# blues-hardware.net
KiCad netlist of a schematic drawn in EAGLE
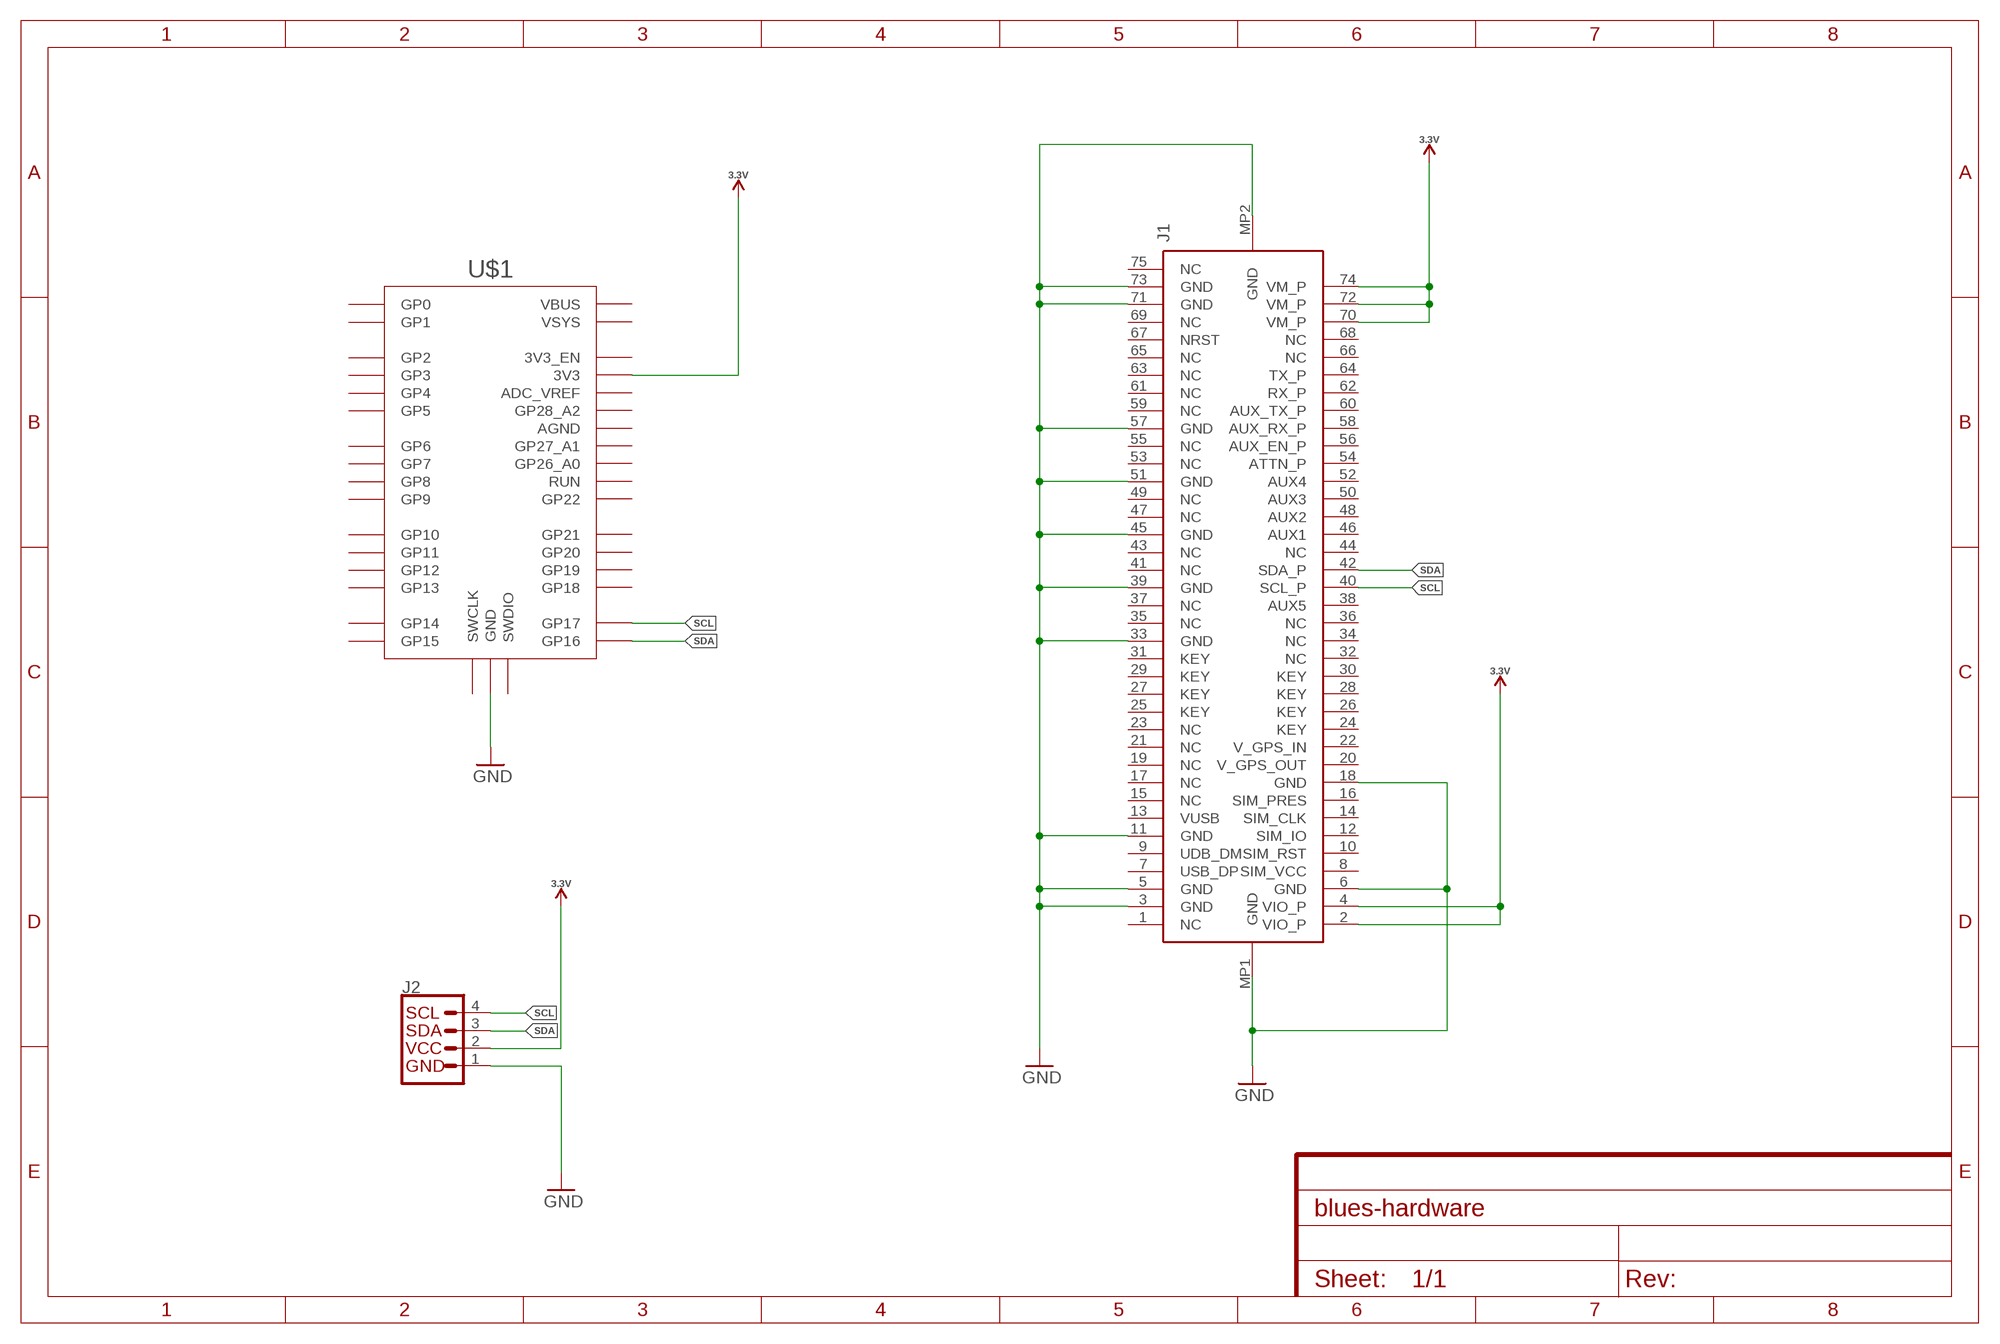
[diagram p0: schematic, sheet 1]

(export (version "E")
  (design (tool "Eeschema 10.0.6"))
  (components
    (comp (ref "J1")
      (value "MDT420E01001NOTECARD")
      (footprint "eagle-import:NOTECARD")
      (libsource (lib "eagle-import") (part "MDT420E01001NOTECARD"))
    )
    (comp (ref "J2")
      (value "QWIIC_CONNECTORJS-1MM")
      (footprint "eagle-import:1X04_1MM_RA")
      (libsource (lib "eagle-import") (part "QWIIC_CONNECTORJS-1MM"))
    )
    (comp (ref "U$1")
      (value "RPI_PICO-TH")
      (footprint "eagle-import:RPI_PICO_TH")
      (libsource (lib "eagle-import") (part "RPI_PICO-TH"))
    )
  )
  (nets
    (net (code "1") (name "3.3V") (class "Default")
      (node (ref "J1") (pin "2") (pinfunction "VIO_P_2") (pintype "bidirectional"))
      (node (ref "J1") (pin "4") (pinfunction "VIO_P_4") (pintype "bidirectional"))
      (node (ref "J1") (pin "70") (pinfunction "VM_P_70") (pintype "bidirectional"))
      (node (ref "J1") (pin "72") (pinfunction "VM_P_72") (pintype "bidirectional"))
      (node (ref "J1") (pin "74") (pinfunction "VM_P_74") (pintype "bidirectional"))
      (node (ref "J2") (pin "2") (pinfunction "2_2") (pintype "power_in"))
      (node (ref "U$1") (pin "3V3") (pinfunction "3V3_3V3") (pintype "bidirectional"))
    )
    (net (code "2") (name "GND") (class "Default")
      (node (ref "J1") (pin "11") (pinfunction "GND_11") (pintype "bidirectional"))
      (node (ref "J1") (pin "18") (pinfunction "GND_18") (pintype "bidirectional"))
      (node (ref "J1") (pin "3") (pinfunction "GND_3") (pintype "bidirectional"))
      (node (ref "J1") (pin "33") (pinfunction "GND_33") (pintype "bidirectional"))
      (node (ref "J1") (pin "39") (pinfunction "GND_39") (pintype "bidirectional"))
      (node (ref "J1") (pin "45") (pinfunction "GND_45") (pintype "bidirectional"))
      (node (ref "J1") (pin "5") (pinfunction "GND_5") (pintype "bidirectional"))
      (node (ref "J1") (pin "51") (pinfunction "GND_51") (pintype "bidirectional"))
      (node (ref "J1") (pin "57") (pinfunction "GND_57") (pintype "bidirectional"))
      (node (ref "J1") (pin "6") (pinfunction "GND_6") (pintype "bidirectional"))
      (node (ref "J1") (pin "71") (pinfunction "GND_71") (pintype "bidirectional"))
      (node (ref "J1") (pin "73") (pinfunction "GND_73") (pintype "bidirectional"))
      (node (ref "J1") (pin "MP1") (pinfunction "GND_MP1") (pintype "power_in"))
      (node (ref "J1") (pin "MP2") (pinfunction "GND_MP2") (pintype "bidirectional"))
      (node (ref "J2") (pin "1") (pinfunction "1_1") (pintype "power_in"))
      (node (ref "U$1") (pin "GND@1") (pinfunction "GND_GND@1") (pintype "bidirectional"))
      (node (ref "U$1") (pin "GND@2") (pinfunction "GND_GND@2") (pintype "bidirectional"))
      (node (ref "U$1") (pin "GND@3") (pinfunction "GND_GND@3") (pintype "bidirectional"))
      (node (ref "U$1") (pin "GND@4") (pinfunction "GND_GND@4") (pintype "bidirectional"))
      (node (ref "U$1") (pin "GND@5") (pinfunction "GND_GND@5") (pintype "bidirectional"))
      (node (ref "U$1") (pin "GND@6") (pinfunction "GND_GND@6") (pintype "bidirectional"))
      (node (ref "U$1") (pin "GND@7") (pinfunction "GND_GND@7") (pintype "bidirectional"))
      (node (ref "U$1") (pin "GND@8") (pinfunction "GND_GND@8") (pintype "bidirectional"))
    )
    (net (code "3") (name "SCL") (class "Default")
      (node (ref "J1") (pin "40") (pinfunction "SCL_P_40") (pintype "bidirectional"))
      (node (ref "J2") (pin "4") (pinfunction "4_4") (pintype "passive"))
      (node (ref "U$1") (pin "GP17") (pinfunction "GP17_GP17") (pintype "bidirectional"))
    )
    (net (code "4") (name "SDA") (class "Default")
      (node (ref "J1") (pin "42") (pinfunction "SDA_P_42") (pintype "bidirectional"))
      (node (ref "J2") (pin "3") (pinfunction "3_3") (pintype "passive"))
      (node (ref "U$1") (pin "GP16") (pinfunction "GP16_GP16") (pintype "bidirectional"))
    )
    (net (code "5") (name "unconnected-(J1-ATTN_P-Pad54)") (class "Default")
      (node (ref "J1") (pin "54") (pinfunction "ATTN_P_54") (pintype "bidirectional"))
    )
    (net (code "6") (name "unconnected-(J1-AUX1-Pad46)") (class "Default")
      (node (ref "J1") (pin "46") (pinfunction "AUX1_46") (pintype "bidirectional"))
    )
    (net (code "7") (name "unconnected-(J1-AUX2-Pad48)") (class "Default")
      (node (ref "J1") (pin "48") (pinfunction "AUX2_48") (pintype "bidirectional"))
    )
    (net (code "8") (name "unconnected-(J1-AUX3-Pad50)") (class "Default")
      (node (ref "J1") (pin "50") (pinfunction "AUX3_50") (pintype "bidirectional"))
    )
    (net (code "9") (name "unconnected-(J1-AUX4-Pad52)") (class "Default")
      (node (ref "J1") (pin "52") (pinfunction "AUX4_52") (pintype "bidirectional"))
    )
    (net (code "10") (name "unconnected-(J1-AUX5-Pad38)") (class "Default")
      (node (ref "J1") (pin "38") (pinfunction "AUX5_38") (pintype "bidirectional"))
    )
    (net (code "11") (name "unconnected-(J1-AUX_EN_P-Pad56)") (class "Default")
      (node (ref "J1") (pin "56") (pinfunction "AUX_EN_P_56") (pintype "bidirectional"))
    )
    (net (code "12") (name "unconnected-(J1-AUX_RX_P-Pad58)") (class "Default")
      (node (ref "J1") (pin "58") (pinfunction "AUX_RX_P_58") (pintype "bidirectional"))
    )
    (net (code "13") (name "unconnected-(J1-AUX_TX_P-Pad60)") (class "Default")
      (node (ref "J1") (pin "60") (pinfunction "AUX_TX_P_60") (pintype "bidirectional"))
    )
    (net (code "14") (name "unconnected-(J1-KEY-Pad24)") (class "Default")
      (node (ref "J1") (pin "24") (pinfunction "KEY_24") (pintype "bidirectional"))
    )
    (net (code "15") (name "unconnected-(J1-KEY-Pad25)") (class "Default")
      (node (ref "J1") (pin "25") (pinfunction "KEY_25") (pintype "bidirectional"))
    )
    (net (code "16") (name "unconnected-(J1-KEY-Pad26)") (class "Default")
      (node (ref "J1") (pin "26") (pinfunction "KEY_26") (pintype "bidirectional"))
    )
    (net (code "17") (name "unconnected-(J1-KEY-Pad27)") (class "Default")
      (node (ref "J1") (pin "27") (pinfunction "KEY_27") (pintype "bidirectional"))
    )
    (net (code "18") (name "unconnected-(J1-KEY-Pad28)") (class "Default")
      (node (ref "J1") (pin "28") (pinfunction "KEY_28") (pintype "bidirectional"))
    )
    (net (code "19") (name "unconnected-(J1-KEY-Pad29)") (class "Default")
      (node (ref "J1") (pin "29") (pinfunction "KEY_29") (pintype "bidirectional"))
    )
    (net (code "20") (name "unconnected-(J1-KEY-Pad30)") (class "Default")
      (node (ref "J1") (pin "30") (pinfunction "KEY_30") (pintype "bidirectional"))
    )
    (net (code "21") (name "unconnected-(J1-KEY-Pad31)") (class "Default")
      (node (ref "J1") (pin "31") (pinfunction "KEY_31") (pintype "bidirectional"))
    )
    (net (code "22") (name "unconnected-(J1-NC-Pad1)") (class "Default")
      (node (ref "J1") (pin "1") (pinfunction "NC_1") (pintype "bidirectional"))
    )
    (net (code "23") (name "unconnected-(J1-NC-Pad15)") (class "Default")
      (node (ref "J1") (pin "15") (pinfunction "NC_15") (pintype "bidirectional"))
    )
    (net (code "24") (name "unconnected-(J1-NC-Pad17)") (class "Default")
      (node (ref "J1") (pin "17") (pinfunction "NC_17") (pintype "bidirectional"))
    )
    (net (code "25") (name "unconnected-(J1-NC-Pad19)") (class "Default")
      (node (ref "J1") (pin "19") (pinfunction "NC_19") (pintype "bidirectional"))
    )
    (net (code "26") (name "unconnected-(J1-NC-Pad21)") (class "Default")
      (node (ref "J1") (pin "21") (pinfunction "NC_21") (pintype "bidirectional"))
    )
    (net (code "27") (name "unconnected-(J1-NC-Pad23)") (class "Default")
      (node (ref "J1") (pin "23") (pinfunction "NC_23") (pintype "bidirectional"))
    )
    (net (code "28") (name "unconnected-(J1-NC-Pad32)") (class "Default")
      (node (ref "J1") (pin "32") (pinfunction "NC_32") (pintype "bidirectional"))
    )
    (net (code "29") (name "unconnected-(J1-NC-Pad34)") (class "Default")
      (node (ref "J1") (pin "34") (pinfunction "NC_34") (pintype "bidirectional"))
    )
    (net (code "30") (name "unconnected-(J1-NC-Pad35)") (class "Default")
      (node (ref "J1") (pin "35") (pinfunction "NC_35") (pintype "bidirectional"))
    )
    (net (code "31") (name "unconnected-(J1-NC-Pad36)") (class "Default")
      (node (ref "J1") (pin "36") (pinfunction "NC_36") (pintype "bidirectional"))
    )
    (net (code "32") (name "unconnected-(J1-NC-Pad37)") (class "Default")
      (node (ref "J1") (pin "37") (pinfunction "NC_37") (pintype "bidirectional"))
    )
    (net (code "33") (name "unconnected-(J1-NC-Pad41)") (class "Default")
      (node (ref "J1") (pin "41") (pinfunction "NC_41") (pintype "bidirectional"))
    )
    (net (code "34") (name "unconnected-(J1-NC-Pad43)") (class "Default")
      (node (ref "J1") (pin "43") (pinfunction "NC_43") (pintype "bidirectional"))
    )
    (net (code "35") (name "unconnected-(J1-NC-Pad44)") (class "Default")
      (node (ref "J1") (pin "44") (pinfunction "NC_44") (pintype "bidirectional"))
    )
    (net (code "36") (name "unconnected-(J1-NC-Pad47)") (class "Default")
      (node (ref "J1") (pin "47") (pinfunction "NC_47") (pintype "bidirectional"))
    )
    (net (code "37") (name "unconnected-(J1-NC-Pad49)") (class "Default")
      (node (ref "J1") (pin "49") (pinfunction "NC_49") (pintype "bidirectional"))
    )
    (net (code "38") (name "unconnected-(J1-NC-Pad53)") (class "Default")
      (node (ref "J1") (pin "53") (pinfunction "NC_53") (pintype "bidirectional"))
    )
    (net (code "39") (name "unconnected-(J1-NC-Pad55)") (class "Default")
      (node (ref "J1") (pin "55") (pinfunction "NC_55") (pintype "bidirectional"))
    )
    (net (code "40") (name "unconnected-(J1-NC-Pad59)") (class "Default")
      (node (ref "J1") (pin "59") (pinfunction "NC_59") (pintype "bidirectional"))
    )
    (net (code "41") (name "unconnected-(J1-NC-Pad61)") (class "Default")
      (node (ref "J1") (pin "61") (pinfunction "NC_61") (pintype "bidirectional"))
    )
    (net (code "42") (name "unconnected-(J1-NC-Pad63)") (class "Default")
      (node (ref "J1") (pin "63") (pinfunction "NC_63") (pintype "bidirectional"))
    )
    (net (code "43") (name "unconnected-(J1-NC-Pad65)") (class "Default")
      (node (ref "J1") (pin "65") (pinfunction "NC_65") (pintype "bidirectional"))
    )
    (net (code "44") (name "unconnected-(J1-NC-Pad66)") (class "Default")
      (node (ref "J1") (pin "66") (pinfunction "NC_66") (pintype "bidirectional"))
    )
    (net (code "45") (name "unconnected-(J1-NC-Pad68)") (class "Default")
      (node (ref "J1") (pin "68") (pinfunction "NC_68") (pintype "bidirectional"))
    )
    (net (code "46") (name "unconnected-(J1-NC-Pad69)") (class "Default")
      (node (ref "J1") (pin "69") (pinfunction "NC_69") (pintype "bidirectional"))
    )
    (net (code "47") (name "unconnected-(J1-NC-Pad75)") (class "Default")
      (node (ref "J1") (pin "75") (pinfunction "NC_75") (pintype "bidirectional"))
    )
    (net (code "48") (name "unconnected-(J1-NRST-Pad67)") (class "Default")
      (node (ref "J1") (pin "67") (pinfunction "NRST_67") (pintype "bidirectional"))
    )
    (net (code "49") (name "unconnected-(J1-RX_P-Pad62)") (class "Default")
      (node (ref "J1") (pin "62") (pinfunction "RX_P_62") (pintype "bidirectional"))
    )
    (net (code "50") (name "unconnected-(J1-SIM_CLK-Pad14)") (class "Default")
      (node (ref "J1") (pin "14") (pinfunction "SIM_CLK_14") (pintype "bidirectional"))
    )
    (net (code "51") (name "unconnected-(J1-SIM_IO-Pad12)") (class "Default")
      (node (ref "J1") (pin "12") (pinfunction "SIM_IO_12") (pintype "bidirectional"))
    )
    (net (code "52") (name "unconnected-(J1-SIM_PRES-Pad16)") (class "Default")
      (node (ref "J1") (pin "16") (pinfunction "SIM_PRES_16") (pintype "bidirectional"))
    )
    (net (code "53") (name "unconnected-(J1-SIM_RST-Pad10)") (class "Default")
      (node (ref "J1") (pin "10") (pinfunction "SIM_RST_10") (pintype "bidirectional"))
    )
    (net (code "54") (name "unconnected-(J1-SIM_VCC-Pad8)") (class "Default")
      (node (ref "J1") (pin "8") (pinfunction "SIM_VCC_8") (pintype "bidirectional"))
    )
    (net (code "55") (name "unconnected-(J1-TX_P-Pad64)") (class "Default")
      (node (ref "J1") (pin "64") (pinfunction "TX_P_64") (pintype "bidirectional"))
    )
    (net (code "56") (name "unconnected-(J1-UDB_DM-Pad9)") (class "Default")
      (node (ref "J1") (pin "9") (pinfunction "UDB_DM_9") (pintype "bidirectional"))
    )
    (net (code "57") (name "unconnected-(J1-USB_DP-Pad7)") (class "Default")
      (node (ref "J1") (pin "7") (pinfunction "USB_DP_7") (pintype "bidirectional"))
    )
    (net (code "58") (name "unconnected-(J1-VUSB-Pad13)") (class "Default")
      (node (ref "J1") (pin "13") (pinfunction "VUSB_13") (pintype "bidirectional"))
    )
    (net (code "59") (name "unconnected-(J1-V_GPS_IN-Pad22)") (class "Default")
      (node (ref "J1") (pin "22") (pinfunction "V_GPS_IN_22") (pintype "bidirectional"))
    )
    (net (code "60") (name "unconnected-(J1-V_GPS_OUT-Pad20)") (class "Default")
      (node (ref "J1") (pin "20") (pinfunction "V_GPS_OUT_20") (pintype "bidirectional"))
    )
    (net (code "61") (name "unconnected-(U$1-Pad3V3_EN)") (class "Default")
      (node (ref "U$1") (pin "3V3_EN") (pinfunction "3V3_EN_3V3_EN") (pintype "bidirectional"))
    )
    (net (code "62") (name "unconnected-(U$1-PadADC_VREF)") (class "Default")
      (node (ref "U$1") (pin "ADC_VREF") (pinfunction "ADC_VREF_ADC_VREF") (pintype "bidirectional"))
    )
    (net (code "63") (name "unconnected-(U$1-PadAGND)") (class "Default")
      (node (ref "U$1") (pin "AGND") (pinfunction "AGND_AGND") (pintype "bidirectional"))
    )
    (net (code "64") (name "unconnected-(U$1-PadGP0)") (class "Default")
      (node (ref "U$1") (pin "GP0") (pinfunction "GP0_GP0") (pintype "bidirectional"))
    )
    (net (code "65") (name "unconnected-(U$1-PadGP1)") (class "Default")
      (node (ref "U$1") (pin "GP1") (pinfunction "GP1_GP1") (pintype "bidirectional"))
    )
    (net (code "66") (name "unconnected-(U$1-PadGP2)") (class "Default")
      (node (ref "U$1") (pin "GP2") (pinfunction "GP2_GP2") (pintype "bidirectional"))
    )
    (net (code "67") (name "unconnected-(U$1-PadGP3)") (class "Default")
      (node (ref "U$1") (pin "GP3") (pinfunction "GP3_GP3") (pintype "bidirectional"))
    )
    (net (code "68") (name "unconnected-(U$1-PadGP4)") (class "Default")
      (node (ref "U$1") (pin "GP4") (pinfunction "GP4_GP4") (pintype "bidirectional"))
    )
    (net (code "69") (name "unconnected-(U$1-PadGP5)") (class "Default")
      (node (ref "U$1") (pin "GP5") (pinfunction "GP5_GP5") (pintype "bidirectional"))
    )
    (net (code "70") (name "unconnected-(U$1-PadGP6)") (class "Default")
      (node (ref "U$1") (pin "GP6") (pinfunction "GP6_GP6") (pintype "bidirectional"))
    )
    (net (code "71") (name "unconnected-(U$1-PadGP7)") (class "Default")
      (node (ref "U$1") (pin "GP7") (pinfunction "GP7_GP7") (pintype "bidirectional"))
    )
    (net (code "72") (name "unconnected-(U$1-PadGP8)") (class "Default")
      (node (ref "U$1") (pin "GP8") (pinfunction "GP8_GP8") (pintype "bidirectional"))
    )
    (net (code "73") (name "unconnected-(U$1-PadGP9)") (class "Default")
      (node (ref "U$1") (pin "GP9") (pinfunction "GP9_GP9") (pintype "bidirectional"))
    )
    (net (code "74") (name "unconnected-(U$1-PadGP10)") (class "Default")
      (node (ref "U$1") (pin "GP10") (pinfunction "GP10_GP10") (pintype "bidirectional"))
    )
    (net (code "75") (name "unconnected-(U$1-PadGP11)") (class "Default")
      (node (ref "U$1") (pin "GP11") (pinfunction "GP11_GP11") (pintype "bidirectional"))
    )
    (net (code "76") (name "unconnected-(U$1-PadGP12)") (class "Default")
      (node (ref "U$1") (pin "GP12") (pinfunction "GP12_GP12") (pintype "bidirectional"))
    )
    (net (code "77") (name "unconnected-(U$1-PadGP13)") (class "Default")
      (node (ref "U$1") (pin "GP13") (pinfunction "GP13_GP13") (pintype "bidirectional"))
    )
    (net (code "78") (name "unconnected-(U$1-PadGP14)") (class "Default")
      (node (ref "U$1") (pin "GP14") (pinfunction "GP14_GP14") (pintype "bidirectional"))
    )
    (net (code "79") (name "unconnected-(U$1-PadGP15)") (class "Default")
      (node (ref "U$1") (pin "GP15") (pinfunction "GP15_GP15") (pintype "bidirectional"))
    )
    (net (code "80") (name "unconnected-(U$1-PadGP18)") (class "Default")
      (node (ref "U$1") (pin "GP18") (pinfunction "GP18_GP18") (pintype "bidirectional"))
    )
    (net (code "81") (name "unconnected-(U$1-PadGP19)") (class "Default")
      (node (ref "U$1") (pin "GP19") (pinfunction "GP19_GP19") (pintype "bidirectional"))
    )
    (net (code "82") (name "unconnected-(U$1-PadGP20)") (class "Default")
      (node (ref "U$1") (pin "GP20") (pinfunction "GP20_GP20") (pintype "bidirectional"))
    )
    (net (code "83") (name "unconnected-(U$1-PadGP21)") (class "Default")
      (node (ref "U$1") (pin "GP21") (pinfunction "GP21_GP21") (pintype "bidirectional"))
    )
    (net (code "84") (name "unconnected-(U$1-PadGP22)") (class "Default")
      (node (ref "U$1") (pin "GP22") (pinfunction "GP22_GP22") (pintype "bidirectional"))
    )
    (net (code "85") (name "unconnected-(U$1-PadGP26_A0)") (class "Default")
      (node (ref "U$1") (pin "GP26_A0") (pinfunction "GP26_A0_GP26_A0") (pintype "bidirectional"))
    )
    (net (code "86") (name "unconnected-(U$1-PadGP27_A1)") (class "Default")
      (node (ref "U$1") (pin "GP27_A1") (pinfunction "GP27_A1_GP27_A1") (pintype "bidirectional"))
    )
    (net (code "87") (name "unconnected-(U$1-PadGP28_A2)") (class "Default")
      (node (ref "U$1") (pin "GP28_A2") (pinfunction "GP28_A2_GP28_A2") (pintype "bidirectional"))
    )
    (net (code "88") (name "unconnected-(U$1-PadRUN)") (class "Default")
      (node (ref "U$1") (pin "RUN") (pinfunction "RUN_RUN") (pintype "bidirectional"))
    )
    (net (code "89") (name "unconnected-(U$1-PadSWCLK)") (class "Default")
      (node (ref "U$1") (pin "SWCLK") (pinfunction "SWCLK_SWCLK") (pintype "bidirectional"))
    )
    (net (code "90") (name "unconnected-(U$1-PadSWDIO)") (class "Default")
      (node (ref "U$1") (pin "SWDIO") (pinfunction "SWDIO_SWDIO") (pintype "bidirectional"))
    )
    (net (code "91") (name "unconnected-(U$1-PadVBUS)") (class "Default")
      (node (ref "U$1") (pin "VBUS") (pinfunction "VBUS_VBUS") (pintype "bidirectional"))
    )
    (net (code "92") (name "unconnected-(U$1-PadVSYS)") (class "Default")
      (node (ref "U$1") (pin "VSYS") (pinfunction "VSYS_VSYS") (pintype "bidirectional"))
    )
  )
)
